# Regulator.net
KiCad netlist of a schematic drawn in Altium Designer
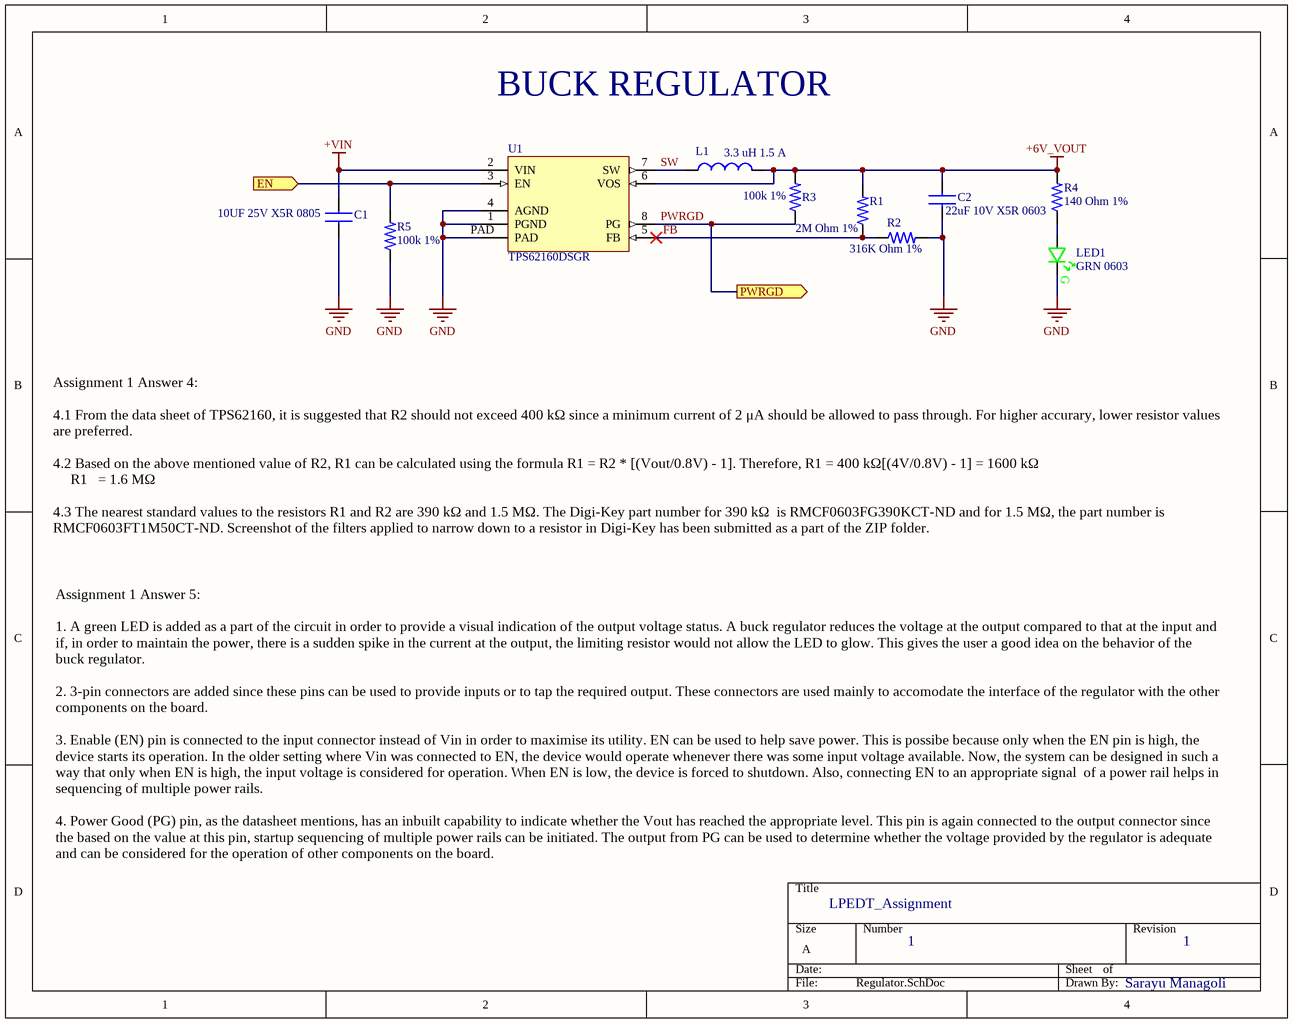
[diagram p0: Regulator.SchDoc]

(export (version "E")
  (design (tool "Eeschema 10.0.6"))
  (components
    (comp (ref "C1")
      (value "10UF 25V X5R 0805")
      (footprint "CAP_2012X14")
      (description "CAP CER 10UF 25V X5R 0805")
      (fields
        (field (name "MANUFACTURER") "Murata")
        (field (name "MANUFACTURER PART NUMBER") "GRM21BR61E106KA73K")
      )
      (libsource (lib "LPEDT_Parts") (part "GRM21BR61E106KA73K"))
    )
    (comp (ref "C2")
      (value "22uF 10V X5R 0603")
      (footprint "CAP_0603_1MM")
      (description "CAP CER 22UF 10V X5R 0603")
      (fields
        (field (name "MANUFACTURER") "Murata")
        (field (name "MANUFACTURER PART NUMBER") "GRM188R61A226ME15D")
      )
      (libsource (lib "LPEDT_Parts") (part "GRM188R61A226ME15D"))
    )
    (comp (ref "L1")
      (value "3.3 uH 1.5 A")
      (footprint "IND_2828x30")
      (fields
        (field (name "MANUFACTURER") "Wurth Electronics")
        (field (name "MANUFACTURER PART NUMBER") "744025003")
        (field (name "TOLERANCE") "20%")
      )
      (libsource (lib "LPEDT_Parts") (part "744025003"))
    )
    (comp (ref "LED1")
      (value "GRN 0603")
      (footprint "LED_0603_GRN_WL-SMCW")
      (description "LED, 0603, GREEN, 430MCD, 520NM")
      (fields
        (field (name "MANUFACTURER") "Wurth Electronics")
        (field (name "MANUFACTURER PART NUMBER") "150060GS75000")
      )
      (libsource (lib "LPEDT_Parts") (part "150060GS75000"))
    )
    (comp (ref "R1")
      (value "2M Ohm 1%")
      (footprint "RES_0603_1608X06")
      (description "Res Thick Film 0603 2M Ohm 1% 0.1W(1/10W) +/-100ppm/ßC Epoxy SMD T/R")
      (fields
        (field (name "MANUFACTURER") "Yageo")
        (field (name "MANUFACTURER PART NUMBER") "RC0603FR-072ML")
      )
      (libsource (lib "LPEDT_Parts") (part "RC0603FR-072ML"))
    )
    (comp (ref "R2")
      (value "316K Ohm 1%")
      (footprint "RES_0603_1608X06")
      (description "Res Thick Film 0603 31.6K Ohm 1% 0.1W(1/10W) ?100ppm/?C Molded SMD Paper T/R")
      (fields
        (field (name "MANUFACTURER") "Yageo")
        (field (name "MANUFACTURER PART NUMBER") "RC0603FR-0731K6L")
      )
      (libsource (lib "LPEDT_Parts") (part "RC0603FR-0731K6L"))
    )
    (comp (ref "R3")
      (value "100k 1%")
      (footprint "RES_0603_1608X06")
      (description "RES SMD 100K OHM 1% 1/10W 0603")
      (fields
        (field (name "MANUFACTURER") "Yageo")
        (field (name "MANUFACTURER PART NUMBER") "RC0603FR-07100KL")
      )
      (libsource (lib "LPEDT_Parts") (part "RC0603FR-07100KL"))
    )
    (comp (ref "R4")
      (value "140 Ohm 1%")
      (footprint "RES_0603_1608X06")
      (description "Thick Film Resistors 140 OHM 1%")
      (fields
        (field (name "MANUFACTURER") "Yageo")
        (field (name "MANUFACTURER PART NUMBER") "RC0603FR-07140RL")
      )
      (libsource (lib "LPEDT_Parts") (part "RC0603FR-07140RL"))
    )
    (comp (ref "R5")
      (value "100k 1%")
      (footprint "RES_0603_1608X06")
      (description "RES SMD 100K OHM 1% 1/10W 0603")
      (fields
        (field (name "MANUFACTURER") "Yageo")
        (field (name "MANUFACTURER PART NUMBER") "RC0603FR-07100KL")
      )
      (libsource (lib "LPEDT_Parts") (part "RC0603FR-07100KL"))
    )
    (comp (ref "U1")
      (value "TPS62160DSGR")
      (footprint "8-DFN_2x2")
      (description "IC REG BUCK ADJ 1A SYNC 8WSON")
      (fields (field (name "MANUFACTURER") "Texas Instruments"))
      (libsource (lib "LPEDT_Parts") (part "TPS62160DSGR"))
    )
  )
  (nets
    (net (code "1") (name "+6V_VOUT") (class "Default")
      (node (ref "C2") (pin "1") (pinfunction "1_1") (pintype "passive"))
      (node (ref "L1") (pin "2") (pinfunction "2_2") (pintype "passive"))
      (node (ref "R1") (pin "2") (pinfunction "2_2") (pintype "passive"))
      (node (ref "R3") (pin "2") (pinfunction "2_2") (pintype "passive"))
      (node (ref "R4") (pin "2") (pinfunction "2_2") (pintype "passive"))
      (node (ref "U1") (pin "6") (pinfunction "VOS_6") (pintype "input"))
    )
    (net (code "2") (name "+VIN") (class "Default")
      (node (ref "C1") (pin "1") (pinfunction "1_1") (pintype "passive"))
      (node (ref "U1") (pin "2") (pinfunction "VIN_2") (pintype "power_in"))
    )
    (net (code "3") (name "/EN") (class "Default")
      (node (ref "R5") (pin "2") (pinfunction "2_2") (pintype "passive"))
      (node (ref "U1") (pin "3") (pinfunction "EN_3") (pintype "input"))
    )
    (net (code "4") (name "/FB") (class "Default")
      (node (ref "R1") (pin "1") (pinfunction "1_1") (pintype "passive"))
      (node (ref "R2") (pin "1") (pinfunction "1_1") (pintype "passive"))
      (node (ref "U1") (pin "5") (pinfunction "FB_5") (pintype "input"))
    )
    (net (code "5") (name "/PWRGD") (class "Default")
      (node (ref "R3") (pin "1") (pinfunction "1_1") (pintype "passive"))
      (node (ref "U1") (pin "8") (pinfunction "PG_8") (pintype "output"))
    )
    (net (code "6") (name "/SW") (class "Default")
      (node (ref "L1") (pin "1") (pinfunction "1_1") (pintype "passive"))
      (node (ref "U1") (pin "7") (pinfunction "SW_7") (pintype "output"))
    )
    (net (code "7") (name "GND") (class "Default")
      (node (ref "C1") (pin "2") (pinfunction "2_2") (pintype "passive"))
      (node (ref "C2") (pin "2") (pinfunction "2_2") (pintype "passive"))
      (node (ref "LED1") (pin "C") (pinfunction "C_C") (pintype "passive"))
      (node (ref "R2") (pin "2") (pinfunction "2_2") (pintype "passive"))
      (node (ref "R5") (pin "1") (pinfunction "1_1") (pintype "passive"))
      (node (ref "U1") (pin "1") (pinfunction "PGND_1") (pintype "power_in"))
      (node (ref "U1") (pin "4") (pinfunction "AGND_4") (pintype "power_in"))
      (node (ref "U1") (pin "PAD") (pinfunction "PAD_PAD") (pintype "power_in"))
    )
    (net (code "8") (name "Net-(LED1-PadA)") (class "Default")
      (node (ref "LED1") (pin "A") (pinfunction "A_A") (pintype "passive"))
      (node (ref "R4") (pin "1") (pinfunction "1_1") (pintype "passive"))
    )
  )
)
